# compare1_2.net
KiCad netlist of a schematic drawn in EAGLE
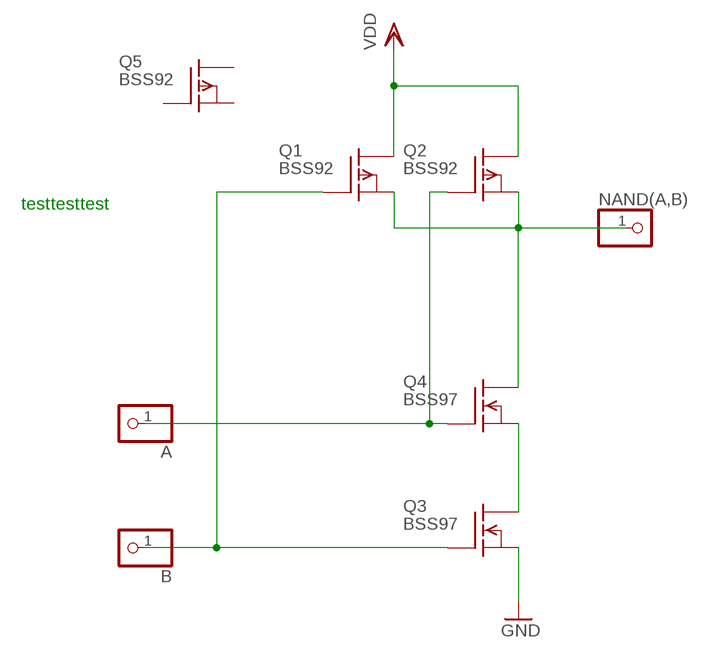
[diagram p0: schematic, sheet 1]

(export (version "E")
  (design (tool "Eeschema 10.0.6"))
  (components
    (comp (ref "A")
      (value "PINHD-1X1")
      (footprint "eagle-import:1X01")
      (libsource (lib "eagle-import") (part "PINHD-1X1"))
    )
    (comp (ref "B")
      (value "PINHD-1X1")
      (footprint "eagle-import:1X01")
      (libsource (lib "eagle-import") (part "PINHD-1X1"))
    )
    (comp (ref "NAND(A,B)")
      (value "PINHD-1X1")
      (footprint "eagle-import:1X01")
      (libsource (lib "eagle-import") (part "PINHD-1X1"))
    )
    (comp (ref "Q1")
      (value "BSS92")
      (footprint "eagle-import:TO92")
      (libsource (lib "eagle-import") (part "BSS92"))
    )
    (comp (ref "Q2")
      (value "BSS92")
      (footprint "eagle-import:TO92")
      (libsource (lib "eagle-import") (part "BSS92"))
    )
    (comp (ref "Q3")
      (value "BSS97")
      (footprint "eagle-import:TO202")
      (libsource (lib "eagle-import") (part "BSS97"))
    )
    (comp (ref "Q4")
      (value "BSS97")
      (footprint "eagle-import:TO202")
      (libsource (lib "eagle-import") (part "BSS97"))
    )
    (comp (ref "Q5")
      (value "BSS92")
      (footprint "eagle-import:TO92")
      (libsource (lib "eagle-import") (part "BSS92"))
    )
  )
  (nets
    (net (code "1") (name "GND") (class "Default")
      (node (ref "Q3") (pin "1") (pinfunction "S_1") (pintype "passive"))
    )
    (net (code "2") (name "Net-(Q1-G)") (class "Default")
      (node (ref "B") (pin "1") (pinfunction "1_1") (pintype "passive"))
      (node (ref "Q1") (pin "1") (pinfunction "G_1") (pintype "passive"))
      (node (ref "Q3") (pin "3") (pinfunction "G_3") (pintype "passive"))
    )
    (net (code "3") (name "Net-(Q1-S)") (class "Default")
      (node (ref "NAND(A,B)") (pin "1") (pinfunction "1_1") (pintype "passive"))
      (node (ref "Q1") (pin "3") (pinfunction "S_3") (pintype "passive"))
      (node (ref "Q2") (pin "3") (pinfunction "S_3") (pintype "passive"))
      (node (ref "Q4") (pin "2") (pinfunction "D_2") (pintype "passive"))
    )
    (net (code "4") (name "Net-(Q2-G)") (class "Default")
      (node (ref "A") (pin "1") (pinfunction "1_1") (pintype "passive"))
      (node (ref "Q2") (pin "1") (pinfunction "G_1") (pintype "passive"))
      (node (ref "Q4") (pin "3") (pinfunction "G_3") (pintype "passive"))
    )
    (net (code "5") (name "Net-(Q3-D)") (class "Default")
      (node (ref "Q3") (pin "2") (pinfunction "D_2") (pintype "passive"))
      (node (ref "Q4") (pin "1") (pinfunction "S_1") (pintype "passive"))
    )
    (net (code "6") (name "VDD") (class "Default")
      (node (ref "Q1") (pin "2") (pinfunction "D_2") (pintype "passive"))
      (node (ref "Q2") (pin "2") (pinfunction "D_2") (pintype "passive"))
    )
    (net (code "7") (name "unconnected-(Q5-D-Pad2)") (class "Default")
      (node (ref "Q5") (pin "2") (pinfunction "D_2") (pintype "passive"))
    )
    (net (code "8") (name "unconnected-(Q5-G-Pad1)") (class "Default")
      (node (ref "Q5") (pin "1") (pinfunction "G_1") (pintype "passive"))
    )
    (net (code "9") (name "unconnected-(Q5-S-Pad3)") (class "Default")
      (node (ref "Q5") (pin "3") (pinfunction "S_3") (pintype "passive"))
    )
  )
)
